# BMS_adapter.net
KiCad netlist of a schematic drawn in EAGLE
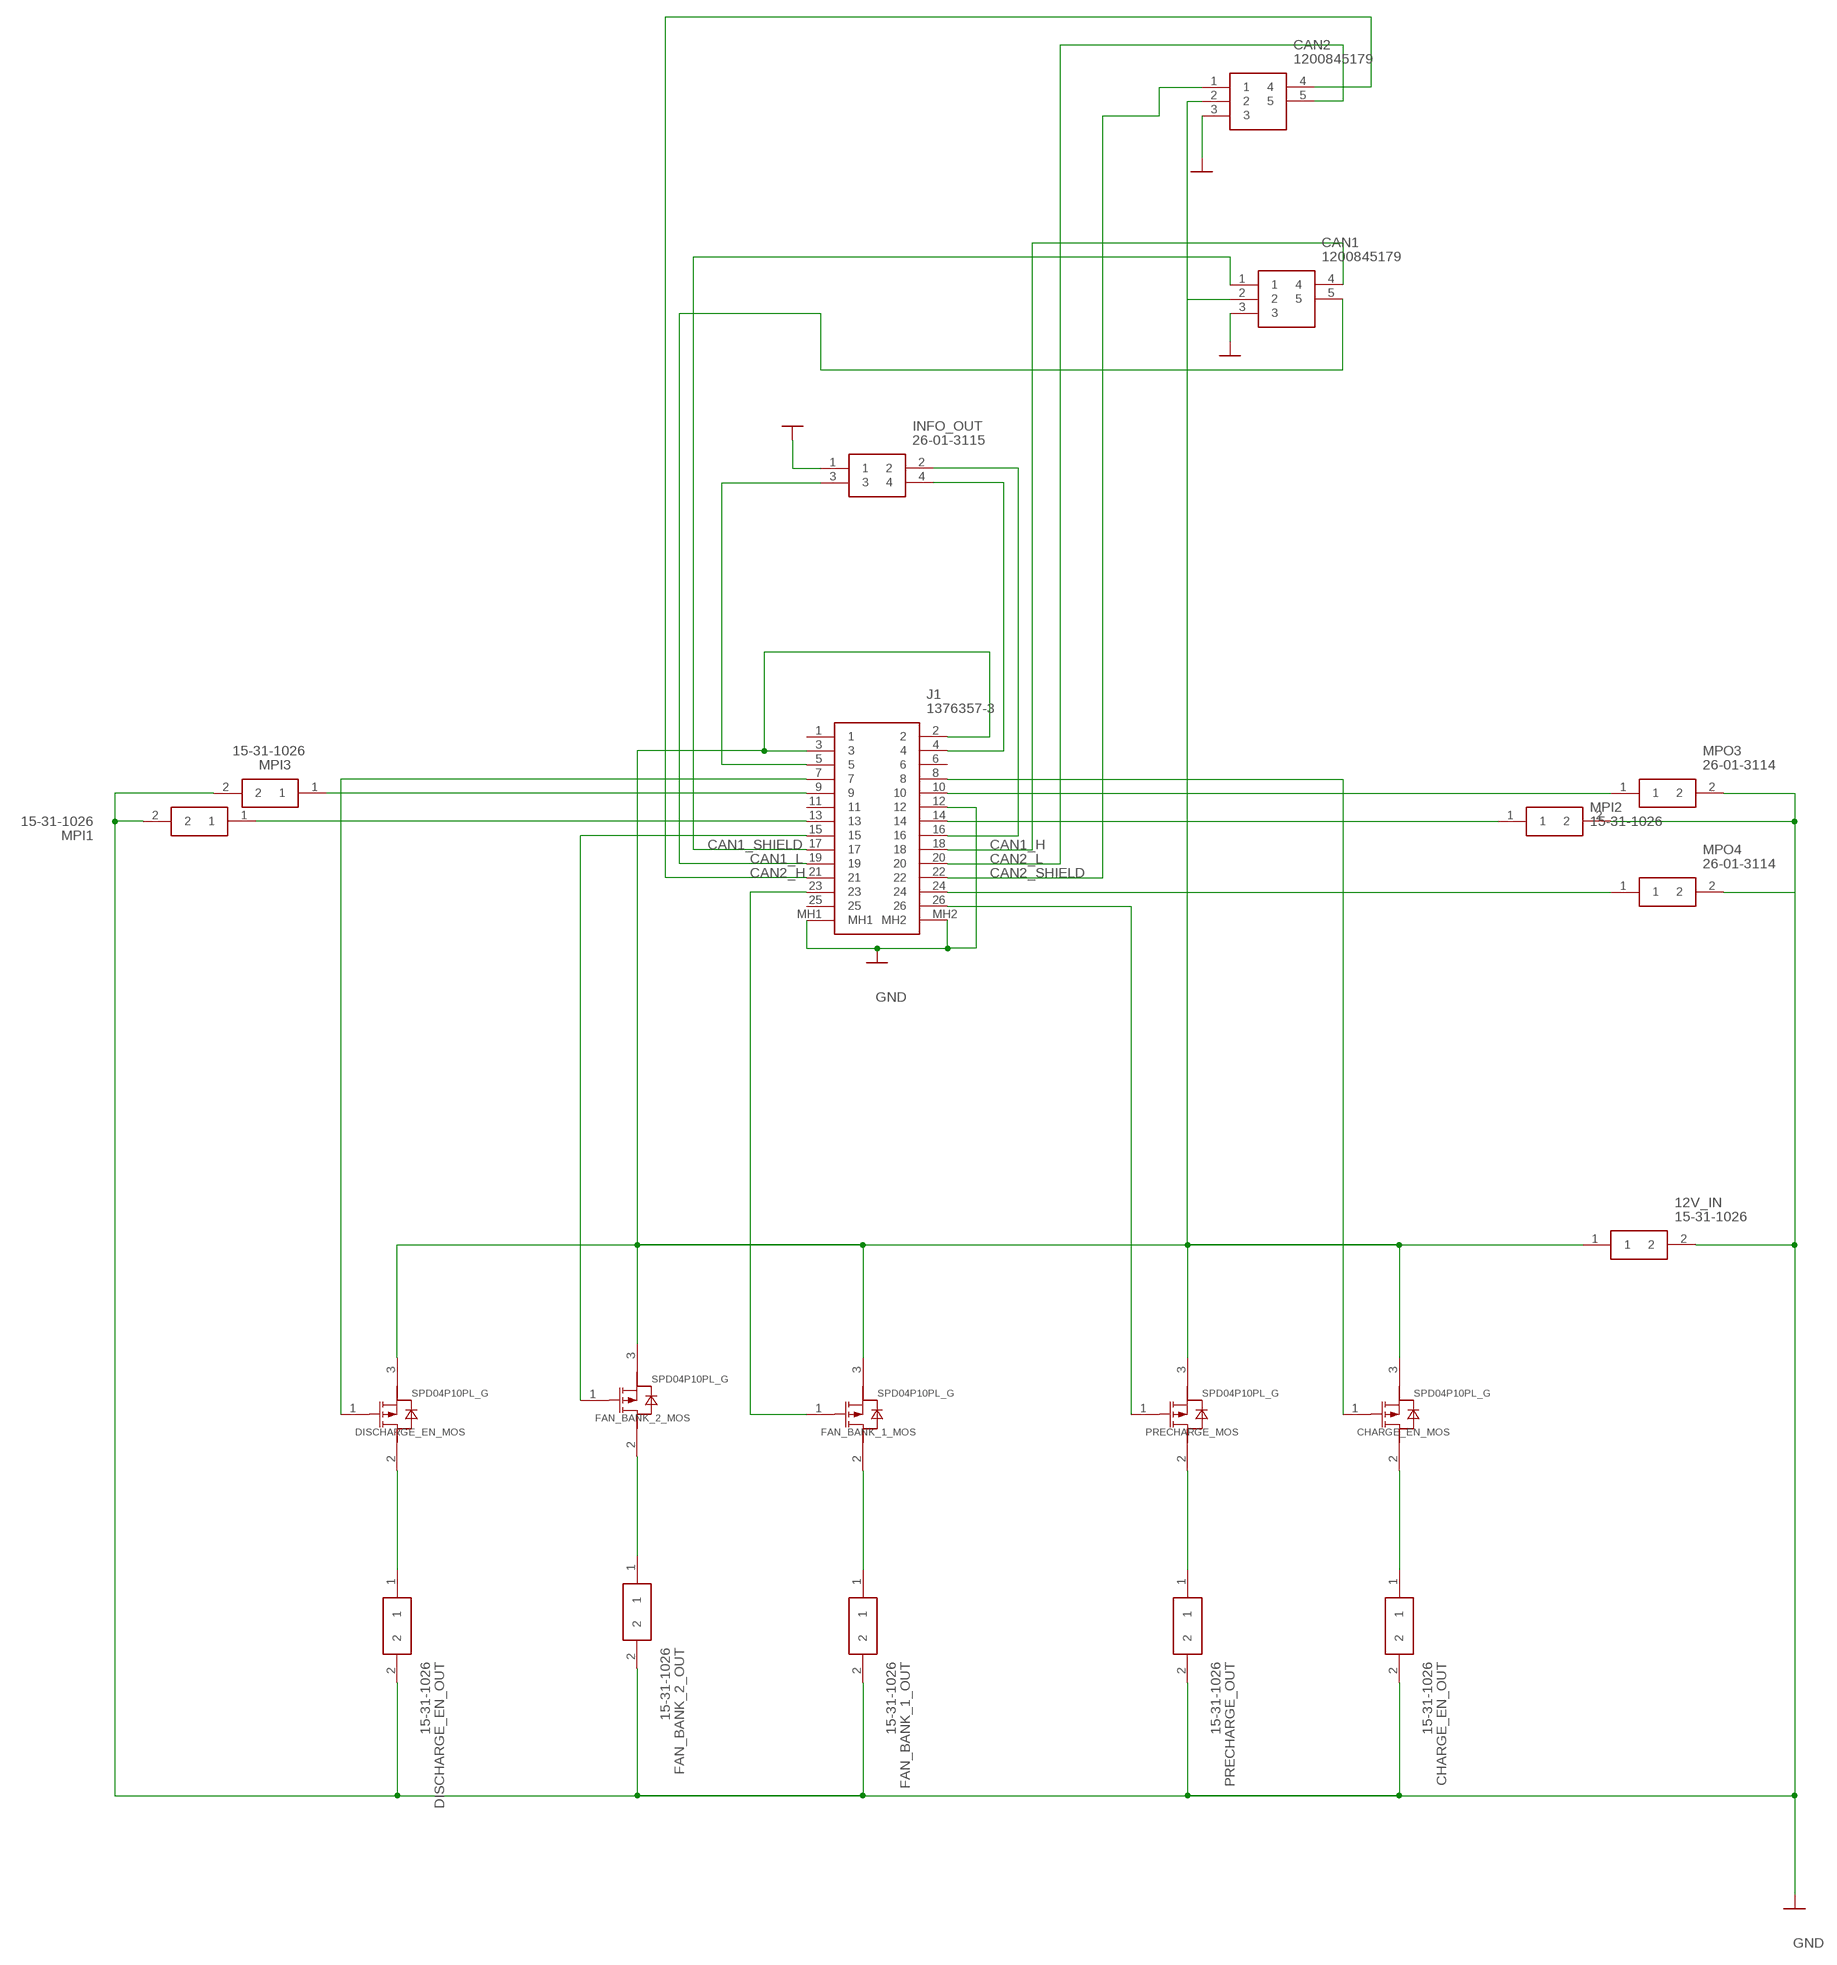
[diagram p0: schematic, sheet 1]

(export (version "E")
  (design (tool "Eeschema 10.0.6"))
  (components
    (comp (ref "12V_IN")
      (value "15-31-1026")
      (footprint "eagle-import:15311026")
      (fields (field (name "MOUSER_PART_NUMBER") "538-15-31-1026") (field (name "RS_PART_NUMBER") "6700289"))
      (libsource (lib "eagle-import") (part "15-31-1026"))
    )
    (comp (ref "CAN1")
      (value "1200845179")
      (footprint "eagle-import:1200845179")
      (fields (field (name "MOUSER_PART_NUMBER") "538-1200845179"))
      (libsource (lib "eagle-import") (part "1200845179"))
    )
    (comp (ref "CAN2")
      (value "1200845179")
      (footprint "eagle-import:1200845179")
      (fields (field (name "MOUSER_PART_NUMBER") "538-1200845179"))
      (libsource (lib "eagle-import") (part "1200845179"))
    )
    (comp (ref "CHARGE_EN_MOS")
      (value "SPD04P10PL_G")
      (footprint "eagle-import:TO229P994X241-3N")
      (libsource (lib "eagle-import") (part "SPD04P10PL_G"))
    )
    (comp (ref "CHARGE_EN_OUT")
      (value "15-31-1026")
      (footprint "eagle-import:15311026")
      (fields (field (name "MOUSER_PART_NUMBER") "538-15-31-1026") (field (name "RS_PART_NUMBER") "6700289"))
      (libsource (lib "eagle-import") (part "15-31-1026"))
    )
    (comp (ref "DISCHARGE_EN_MOS")
      (value "SPD04P10PL_G")
      (footprint "eagle-import:TO229P994X241-3N")
      (libsource (lib "eagle-import") (part "SPD04P10PL_G"))
    )
    (comp (ref "DISCHARGE_EN_OUT")
      (value "15-31-1026")
      (footprint "eagle-import:15311026")
      (fields (field (name "MOUSER_PART_NUMBER") "538-15-31-1026") (field (name "RS_PART_NUMBER") "6700289"))
      (libsource (lib "eagle-import") (part "15-31-1026"))
    )
    (comp (ref "FAN_BANK_1_MOS")
      (value "SPD04P10PL_G")
      (footprint "eagle-import:TO229P994X241-3N")
      (libsource (lib "eagle-import") (part "SPD04P10PL_G"))
    )
    (comp (ref "FAN_BANK_1_OUT")
      (value "15-31-1026")
      (footprint "eagle-import:15311026")
      (fields (field (name "MOUSER_PART_NUMBER") "538-15-31-1026") (field (name "RS_PART_NUMBER") "6700289"))
      (libsource (lib "eagle-import") (part "15-31-1026"))
    )
    (comp (ref "FAN_BANK_2_MOS")
      (value "SPD04P10PL_G")
      (footprint "eagle-import:TO229P994X241-3N")
      (libsource (lib "eagle-import") (part "SPD04P10PL_G"))
    )
    (comp (ref "FAN_BANK_2_OUT")
      (value "15-31-1026")
      (footprint "eagle-import:15311026")
      (fields (field (name "MOUSER_PART_NUMBER") "538-15-31-1026") (field (name "RS_PART_NUMBER") "6700289"))
      (libsource (lib "eagle-import") (part "15-31-1026"))
    )
    (comp (ref "INFO_OUT")
      (value "26-01-3115")
      (footprint "eagle-import:39-30-1040")
      (fields (field (name "MOUSER_PART_NUMBER") "538-26-01-3115"))
      (libsource (lib "eagle-import") (part "26-01-3115"))
    )
    (comp (ref "J1")
      (value "1376357-3")
      (footprint "eagle-import:13763573")
      (fields (field (name "MOUSER_PART_NUMBER") "571-1376357-3"))
      (libsource (lib "eagle-import") (part "1376357-3"))
    )
    (comp (ref "MPI1")
      (value "15-31-1026")
      (footprint "eagle-import:15311026")
      (fields (field (name "MOUSER_PART_NUMBER") "538-15-31-1026") (field (name "RS_PART_NUMBER") "6700289"))
      (libsource (lib "eagle-import") (part "15-31-1026"))
    )
    (comp (ref "MPI2")
      (value "15-31-1026")
      (footprint "eagle-import:15311026")
      (fields (field (name "MOUSER_PART_NUMBER") "538-15-31-1026") (field (name "RS_PART_NUMBER") "6700289"))
      (libsource (lib "eagle-import") (part "15-31-1026"))
    )
    (comp (ref "MPI3")
      (value "15-31-1026")
      (footprint "eagle-import:15311026")
      (fields (field (name "MOUSER_PART_NUMBER") "538-15-31-1026") (field (name "RS_PART_NUMBER") "6700289"))
      (libsource (lib "eagle-import") (part "15-31-1026"))
    )
    (comp (ref "MPO3")
      (value "26-01-3114")
      (footprint "eagle-import:0026013114")
      (fields (field (name "MOUSER_PART_NUMBER") "538-26-01-3114") (field (name "RS_PART_NUMBER") "1791870P"))
      (libsource (lib "eagle-import") (part "26-01-3114"))
    )
    (comp (ref "MPO4")
      (value "26-01-3114")
      (footprint "eagle-import:0026013114")
      (fields (field (name "MOUSER_PART_NUMBER") "538-26-01-3114") (field (name "RS_PART_NUMBER") "1791870P"))
      (libsource (lib "eagle-import") (part "26-01-3114"))
    )
    (comp (ref "PRECHARGE_MOS")
      (value "SPD04P10PL_G")
      (footprint "eagle-import:TO229P994X241-3N")
      (libsource (lib "eagle-import") (part "SPD04P10PL_G"))
    )
    (comp (ref "PRECHARGE_OUT")
      (value "15-31-1026")
      (footprint "eagle-import:15311026")
      (fields (field (name "MOUSER_PART_NUMBER") "538-15-31-1026") (field (name "RS_PART_NUMBER") "6700289"))
      (libsource (lib "eagle-import") (part "15-31-1026"))
    )
  )
  (nets
    (net (code "1") (name "/CAN1_H") (class "Default")
      (node (ref "CAN1") (pin "4") (pinfunction "4_4") (pintype "bidirectional"))
      (node (ref "J1") (pin "18") (pinfunction "18_18") (pintype "bidirectional"))
    )
    (net (code "2") (name "/CAN1_L") (class "Default")
      (node (ref "CAN1") (pin "5") (pinfunction "5_5") (pintype "bidirectional"))
      (node (ref "J1") (pin "19") (pinfunction "19_19") (pintype "bidirectional"))
    )
    (net (code "3") (name "/CAN1_SHIELD") (class "Default")
      (node (ref "CAN1") (pin "1") (pinfunction "1_1") (pintype "bidirectional"))
      (node (ref "J1") (pin "17") (pinfunction "17_17") (pintype "bidirectional"))
    )
    (net (code "4") (name "/CAN2_H") (class "Default")
      (node (ref "CAN2") (pin "4") (pinfunction "4_4") (pintype "bidirectional"))
      (node (ref "J1") (pin "21") (pinfunction "21_21") (pintype "bidirectional"))
    )
    (net (code "5") (name "/CAN2_L") (class "Default")
      (node (ref "CAN2") (pin "5") (pinfunction "5_5") (pintype "bidirectional"))
      (node (ref "J1") (pin "20") (pinfunction "20_20") (pintype "bidirectional"))
    )
    (net (code "6") (name "/CAN2_SHIELD") (class "Default")
      (node (ref "CAN2") (pin "1") (pinfunction "1_1") (pintype "bidirectional"))
      (node (ref "J1") (pin "22") (pinfunction "22_22") (pintype "bidirectional"))
    )
    (net (code "7") (name "GND") (class "Default")
      (node (ref "12V_IN") (pin "2") (pinfunction "2_2") (pintype "bidirectional"))
      (node (ref "CAN1") (pin "3") (pinfunction "3_3") (pintype "bidirectional"))
      (node (ref "CAN2") (pin "3") (pinfunction "3_3") (pintype "bidirectional"))
      (node (ref "CHARGE_EN_OUT") (pin "2") (pinfunction "2_2") (pintype "bidirectional"))
      (node (ref "DISCHARGE_EN_OUT") (pin "2") (pinfunction "2_2") (pintype "bidirectional"))
      (node (ref "FAN_BANK_1_OUT") (pin "2") (pinfunction "2_2") (pintype "bidirectional"))
      (node (ref "FAN_BANK_2_OUT") (pin "2") (pinfunction "2_2") (pintype "bidirectional"))
      (node (ref "INFO_OUT") (pin "1") (pinfunction "1_1") (pintype "bidirectional"))
      (node (ref "J1") (pin "12") (pinfunction "12_12") (pintype "bidirectional"))
      (node (ref "J1") (pin "MH1") (pinfunction "MH1_MH1") (pintype "bidirectional"))
      (node (ref "J1") (pin "MH2") (pinfunction "MH2_MH2") (pintype "bidirectional"))
      (node (ref "MPI1") (pin "2") (pinfunction "2_2") (pintype "bidirectional"))
      (node (ref "MPI2") (pin "2") (pinfunction "2_2") (pintype "bidirectional"))
      (node (ref "MPI3") (pin "2") (pinfunction "2_2") (pintype "bidirectional"))
      (node (ref "MPO3") (pin "2") (pinfunction "2_2") (pintype "bidirectional"))
      (node (ref "PRECHARGE_OUT") (pin "2") (pinfunction "2_2") (pintype "bidirectional"))
    )
    (net (code "8") (name "Net-(12V_IN-Pad1)") (class "Default")
      (node (ref "12V_IN") (pin "1") (pinfunction "1_1") (pintype "bidirectional"))
      (node (ref "CAN1") (pin "2") (pinfunction "2_2") (pintype "bidirectional"))
      (node (ref "CAN2") (pin "2") (pinfunction "2_2") (pintype "bidirectional"))
      (node (ref "CHARGE_EN_MOS") (pin "3") (pinfunction "3_3") (pintype "passive"))
      (node (ref "DISCHARGE_EN_MOS") (pin "3") (pinfunction "3_3") (pintype "passive"))
      (node (ref "FAN_BANK_1_MOS") (pin "3") (pinfunction "3_3") (pintype "passive"))
      (node (ref "FAN_BANK_2_MOS") (pin "3") (pinfunction "3_3") (pintype "passive"))
      (node (ref "J1") (pin "2") (pinfunction "2_2") (pintype "bidirectional"))
      (node (ref "J1") (pin "3") (pinfunction "3_3") (pintype "bidirectional"))
      (node (ref "PRECHARGE_MOS") (pin "3") (pinfunction "3_3") (pintype "passive"))
    )
    (net (code "9") (name "Net-(CHARGE_EN_MOS-Pad1)") (class "Default")
      (node (ref "CHARGE_EN_MOS") (pin "1") (pinfunction "1_1") (pintype "passive"))
      (node (ref "J1") (pin "8") (pinfunction "8_8") (pintype "bidirectional"))
    )
    (net (code "10") (name "Net-(CHARGE_EN_MOS-Pad2)") (class "Default")
      (node (ref "CHARGE_EN_MOS") (pin "2") (pinfunction "2_2") (pintype "bidirectional"))
      (node (ref "CHARGE_EN_OUT") (pin "1") (pinfunction "1_1") (pintype "bidirectional"))
    )
    (net (code "11") (name "Net-(DISCHARGE_EN_MOS-Pad1)") (class "Default")
      (node (ref "DISCHARGE_EN_MOS") (pin "1") (pinfunction "1_1") (pintype "passive"))
      (node (ref "J1") (pin "7") (pinfunction "7_7") (pintype "bidirectional"))
    )
    (net (code "12") (name "Net-(DISCHARGE_EN_MOS-Pad2)") (class "Default")
      (node (ref "DISCHARGE_EN_MOS") (pin "2") (pinfunction "2_2") (pintype "bidirectional"))
      (node (ref "DISCHARGE_EN_OUT") (pin "1") (pinfunction "1_1") (pintype "bidirectional"))
    )
    (net (code "13") (name "Net-(FAN_BANK_1_MOS-Pad1)") (class "Default")
      (node (ref "FAN_BANK_1_MOS") (pin "1") (pinfunction "1_1") (pintype "passive"))
      (node (ref "J1") (pin "23") (pinfunction "23_23") (pintype "bidirectional"))
    )
    (net (code "14") (name "Net-(FAN_BANK_1_MOS-Pad2)") (class "Default")
      (node (ref "FAN_BANK_1_MOS") (pin "2") (pinfunction "2_2") (pintype "bidirectional"))
      (node (ref "FAN_BANK_1_OUT") (pin "1") (pinfunction "1_1") (pintype "bidirectional"))
    )
    (net (code "15") (name "Net-(FAN_BANK_2_MOS-Pad1)") (class "Default")
      (node (ref "FAN_BANK_2_MOS") (pin "1") (pinfunction "1_1") (pintype "passive"))
      (node (ref "J1") (pin "15") (pinfunction "15_15") (pintype "bidirectional"))
    )
    (net (code "16") (name "Net-(FAN_BANK_2_MOS-Pad2)") (class "Default")
      (node (ref "FAN_BANK_2_MOS") (pin "2") (pinfunction "2_2") (pintype "bidirectional"))
      (node (ref "FAN_BANK_2_OUT") (pin "1") (pinfunction "1_1") (pintype "bidirectional"))
    )
    (net (code "17") (name "Net-(INFO_OUT-Pad2)") (class "Default")
      (node (ref "INFO_OUT") (pin "2") (pinfunction "2_2") (pintype "bidirectional"))
      (node (ref "J1") (pin "16") (pinfunction "16_16") (pintype "bidirectional"))
    )
    (net (code "18") (name "Net-(INFO_OUT-Pad3)") (class "Default")
      (node (ref "INFO_OUT") (pin "3") (pinfunction "3_3") (pintype "bidirectional"))
      (node (ref "J1") (pin "5") (pinfunction "5_5") (pintype "bidirectional"))
    )
    (net (code "19") (name "Net-(INFO_OUT-Pad4)") (class "Default")
      (node (ref "INFO_OUT") (pin "4") (pinfunction "4_4") (pintype "bidirectional"))
      (node (ref "J1") (pin "4") (pinfunction "4_4") (pintype "bidirectional"))
    )
    (net (code "20") (name "Net-(J1-Pad9)") (class "Default")
      (node (ref "J1") (pin "9") (pinfunction "9_9") (pintype "bidirectional"))
      (node (ref "MPI3") (pin "1") (pinfunction "1_1") (pintype "bidirectional"))
    )
    (net (code "21") (name "Net-(J1-Pad10)") (class "Default")
      (node (ref "J1") (pin "10") (pinfunction "10_10") (pintype "bidirectional"))
      (node (ref "MPO3") (pin "1") (pinfunction "1_1") (pintype "bidirectional"))
    )
    (net (code "22") (name "Net-(J1-Pad13)") (class "Default")
      (node (ref "J1") (pin "13") (pinfunction "13_13") (pintype "bidirectional"))
      (node (ref "MPI1") (pin "1") (pinfunction "1_1") (pintype "bidirectional"))
    )
    (net (code "23") (name "Net-(J1-Pad14)") (class "Default")
      (node (ref "J1") (pin "14") (pinfunction "14_14") (pintype "bidirectional"))
      (node (ref "MPI2") (pin "1") (pinfunction "1_1") (pintype "bidirectional"))
    )
    (net (code "24") (name "Net-(J1-Pad24)") (class "Default")
      (node (ref "J1") (pin "24") (pinfunction "24_24") (pintype "bidirectional"))
      (node (ref "MPO4") (pin "1") (pinfunction "1_1") (pintype "bidirectional"))
    )
    (net (code "25") (name "Net-(J1-Pad26)") (class "Default")
      (node (ref "J1") (pin "26") (pinfunction "26_26") (pintype "bidirectional"))
      (node (ref "PRECHARGE_MOS") (pin "1") (pinfunction "1_1") (pintype "passive"))
    )
    (net (code "26") (name "Net-(PRECHARGE_MOS-Pad2)") (class "Default")
      (node (ref "PRECHARGE_MOS") (pin "2") (pinfunction "2_2") (pintype "bidirectional"))
      (node (ref "PRECHARGE_OUT") (pin "1") (pinfunction "1_1") (pintype "bidirectional"))
    )
    (net (code "27") (name "unconnected-(J1-Pad1)") (class "Default")
      (node (ref "J1") (pin "1") (pinfunction "1_1") (pintype "bidirectional"))
    )
    (net (code "28") (name "unconnected-(J1-Pad6)") (class "Default")
      (node (ref "J1") (pin "6") (pinfunction "6_6") (pintype "bidirectional"))
    )
    (net (code "29") (name "unconnected-(J1-Pad11)") (class "Default")
      (node (ref "J1") (pin "11") (pinfunction "11_11") (pintype "bidirectional"))
    )
    (net (code "30") (name "unconnected-(J1-Pad25)") (class "Default")
      (node (ref "J1") (pin "25") (pinfunction "25_25") (pintype "bidirectional"))
    )
    (net (code "31") (name "unconnected-(MPO4-Pad2)") (class "Default")
      (node (ref "MPO4") (pin "2") (pinfunction "2_2") (pintype "bidirectional"))
    )
  )
)
